# EE445L_Lab_7_Starter.net
KiCad netlist of a schematic drawn in EAGLE
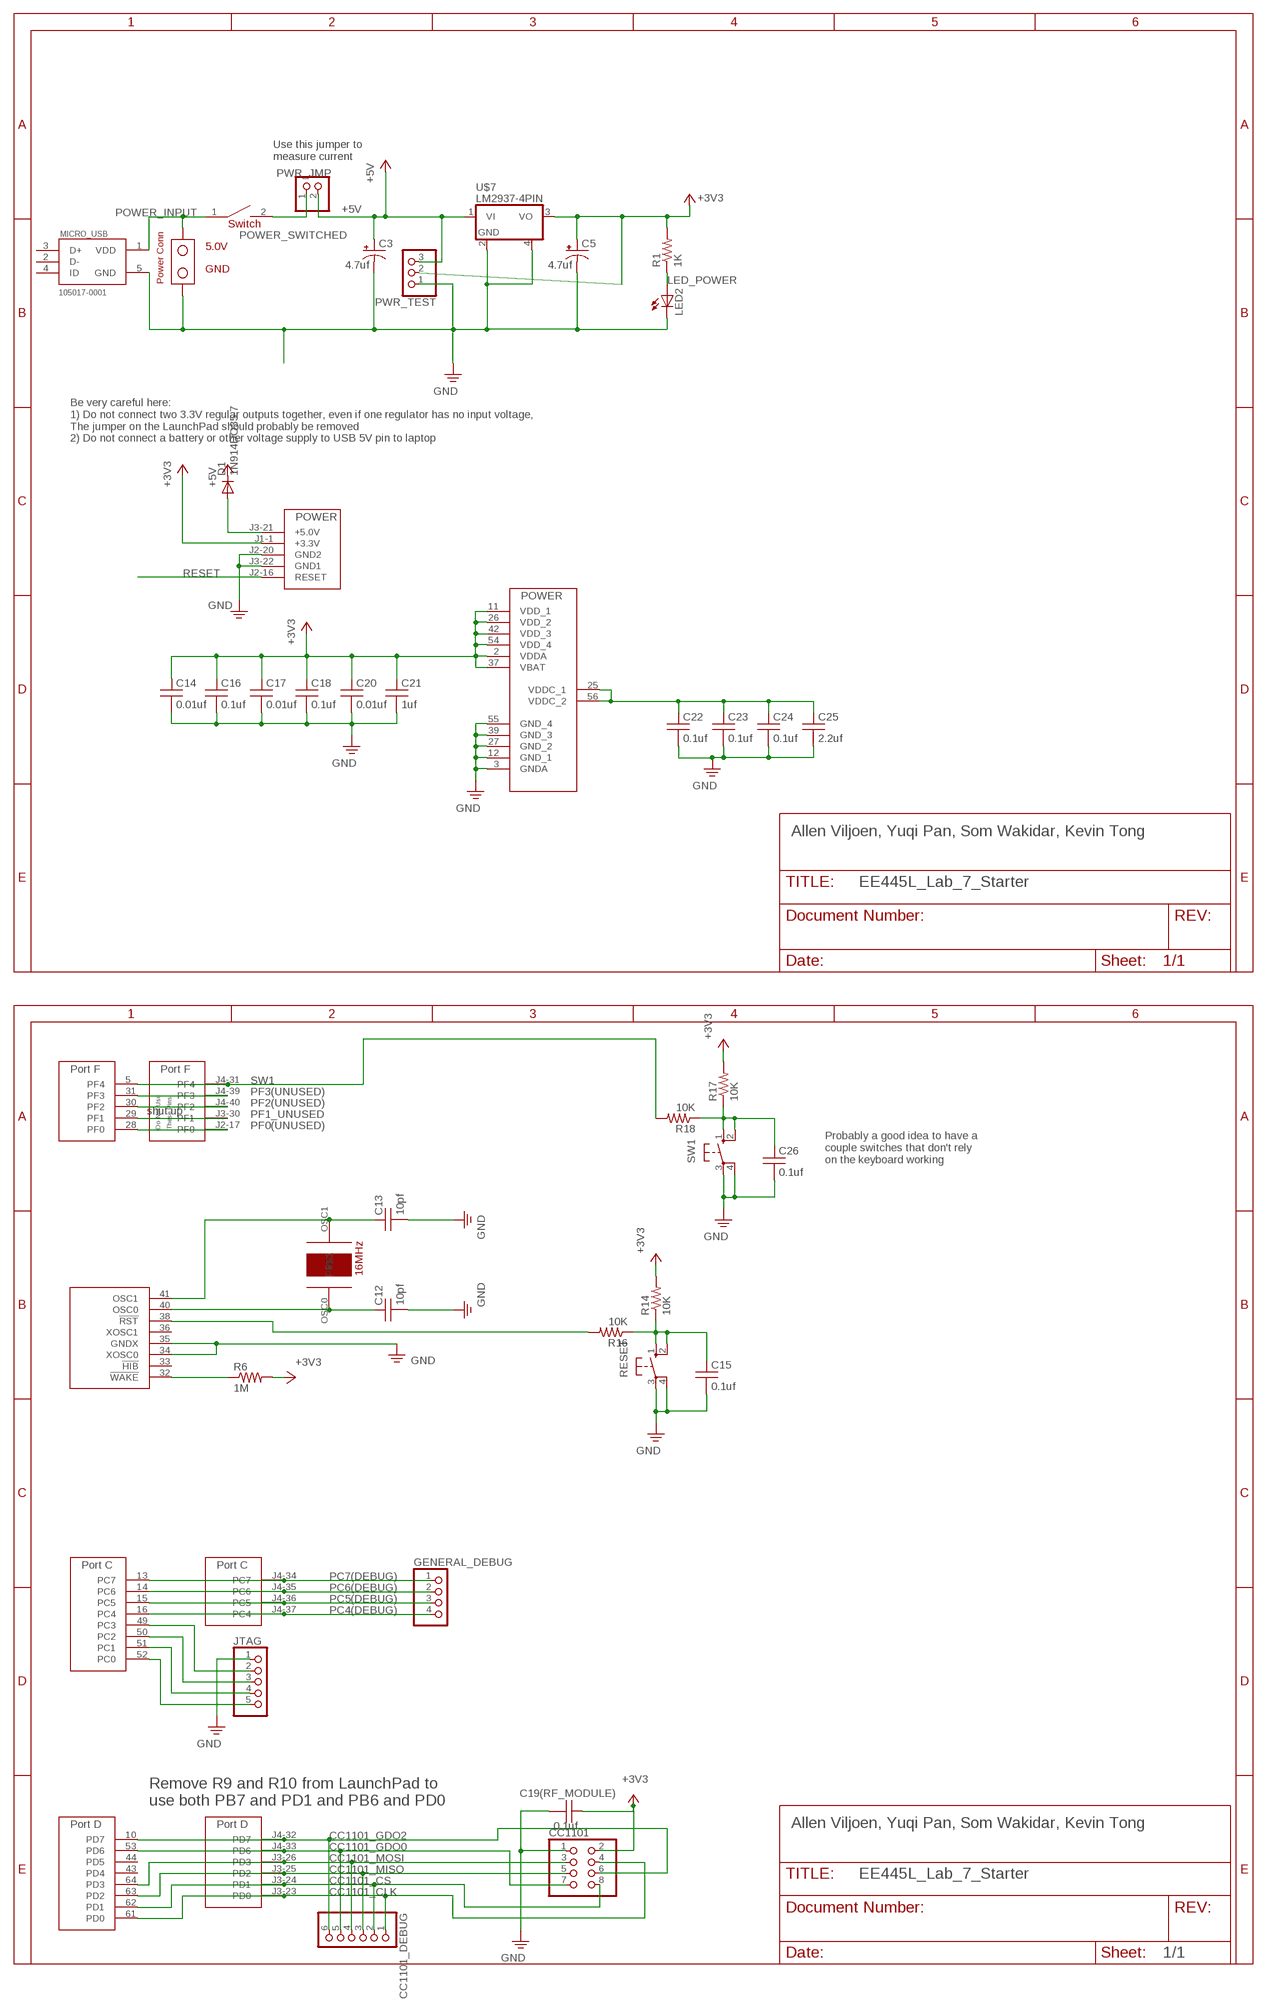
[diagram p0: schematic, sheet 1, part 1 of 2]
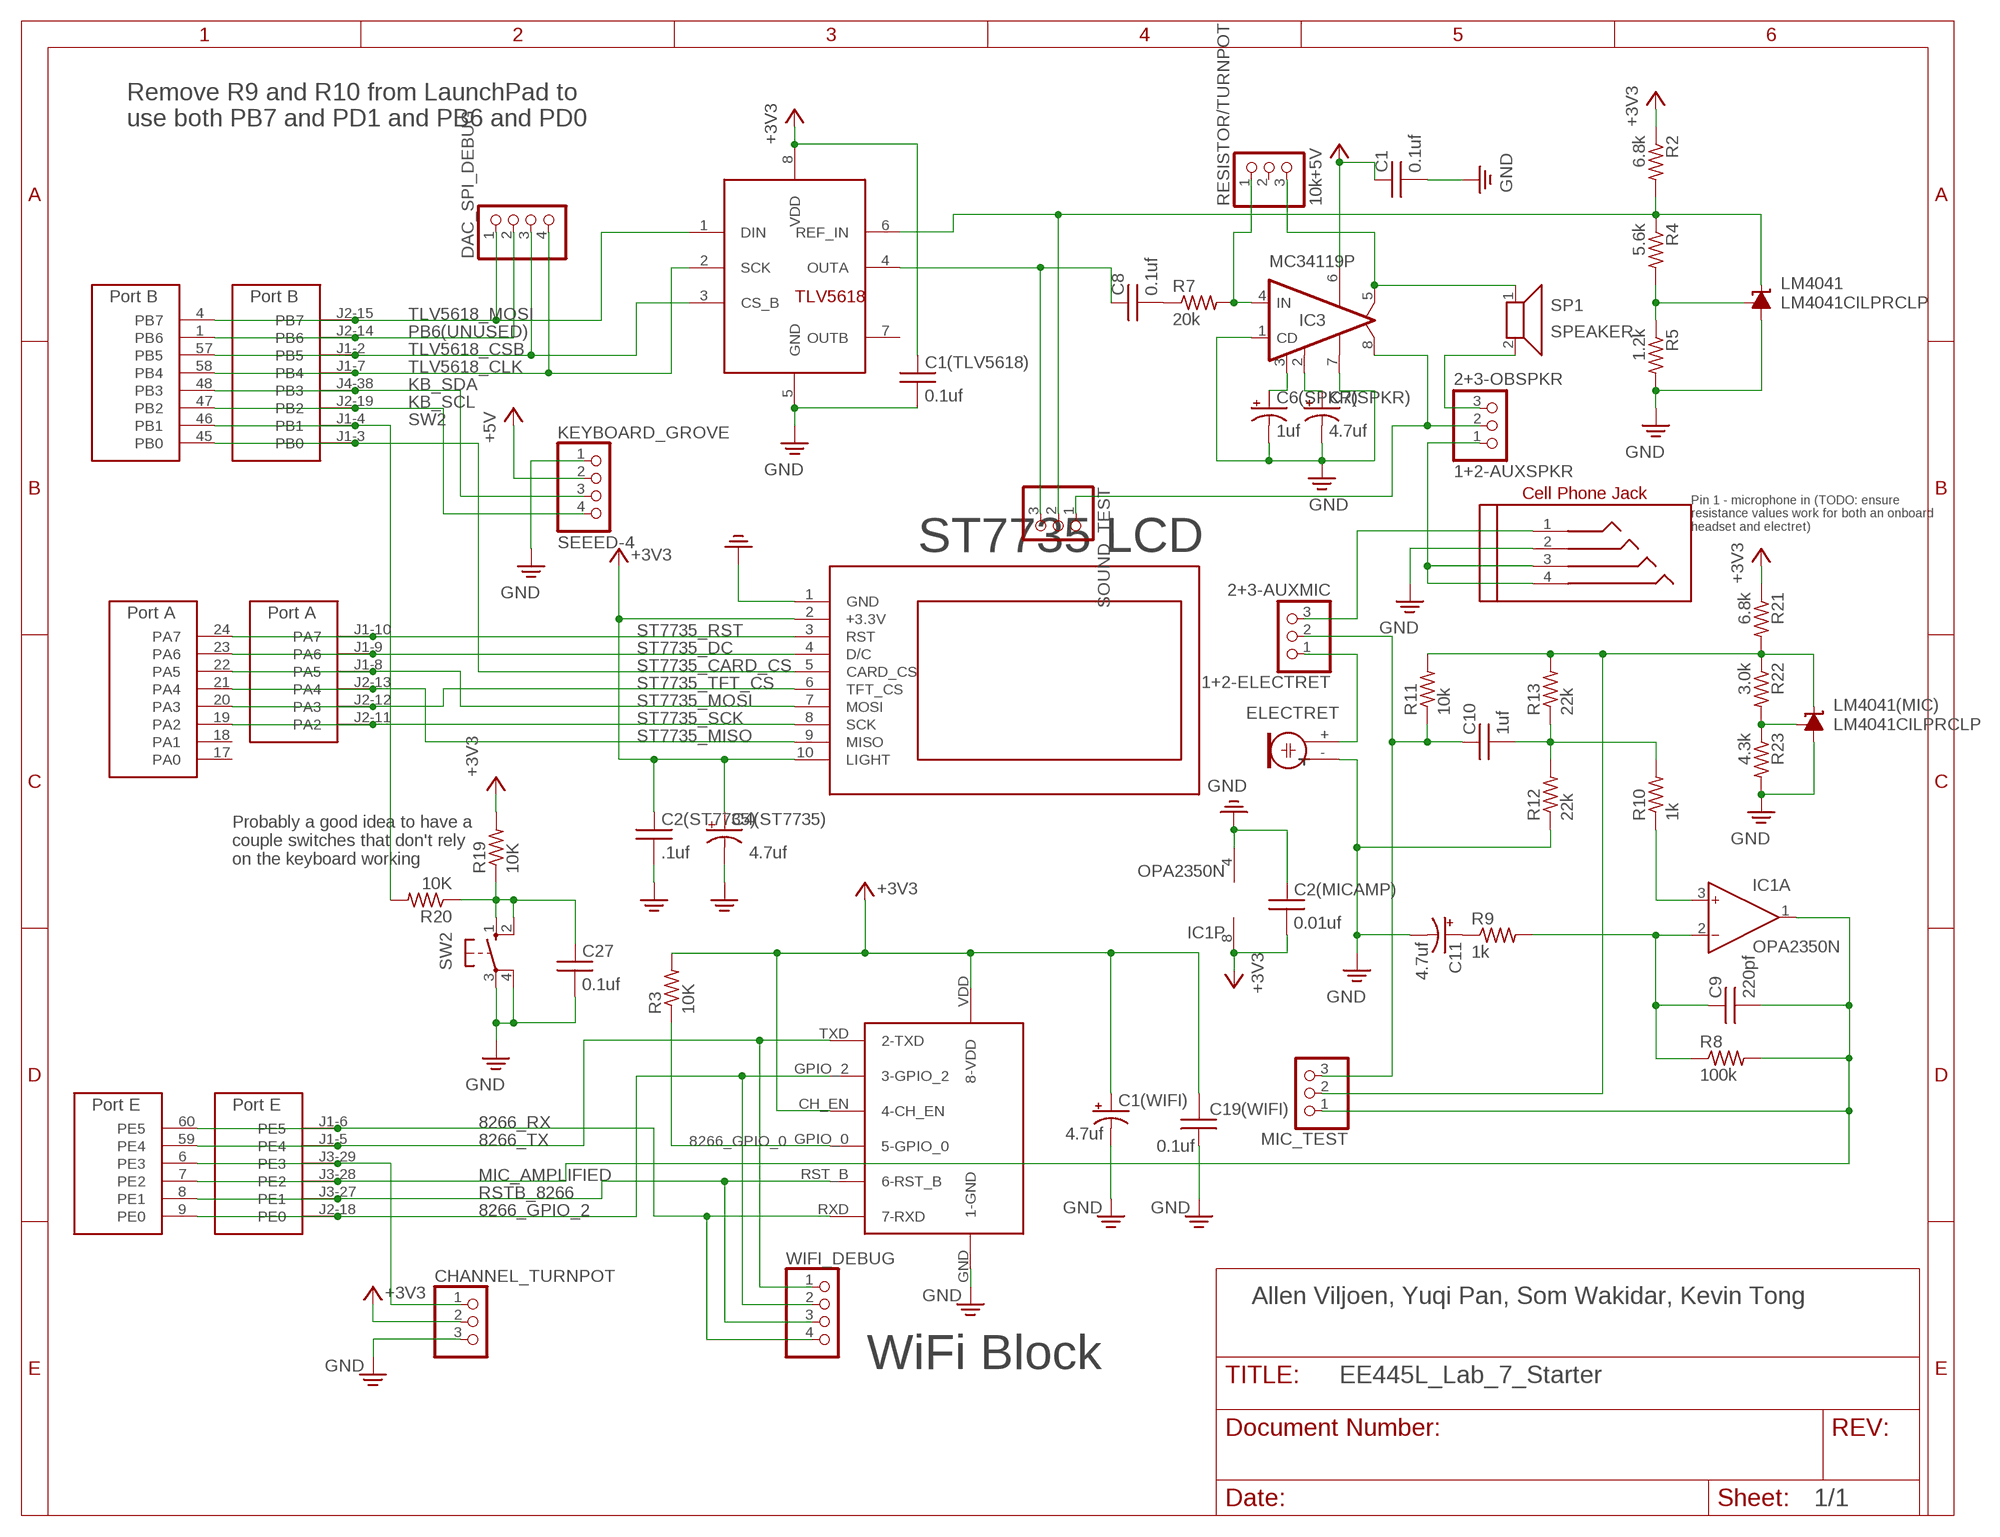
[diagram p1: schematic, sheet 1, part 2 of 2]

(export (version "E")
  (design (tool "Eeschema 10.0.6"))
  (components
    (comp (ref "1+2-AUXSPKR")
      (value "2+3-OBSPKR")
      (footprint "eagle-import:1X03")
      (libsource (lib "eagle-import") (part "PINHD-1X3"))
    )
    (comp (ref "1+2-ELECTRET")
      (value "2+3-AUXMIC")
      (footprint "eagle-import:1X03")
      (libsource (lib "eagle-import") (part "PINHD-1X3"))
    )
    (comp (ref "C1")
      (value "0.1uf")
      (footprint "eagle-import:CAP100MIL")
      (libsource (lib "eagle-import") (part "CAPACITOR025-024X044"))
    )
    (comp (ref "C1(TLV5618)")
      (value "0.1uf")
      (footprint "eagle-import:CAP200MIL")
      (libsource (lib "eagle-import") (part "CAPACITOR050-024X044"))
    )
    (comp (ref "C1(WIFI)")
      (value "4.7uf")
      (footprint "eagle-import:CAP200MILPOLARIZED")
      (libsource (lib "eagle-import") (part "CAPACITOR_POLARIZEDE5-6"))
    )
    (comp (ref "C2(MICAMP)")
      (value "0.01uf")
      (footprint "eagle-import:CAP200MIL")
      (libsource (lib "eagle-import") (part "CAPACITOR050-024X044"))
    )
    (comp (ref "C2(ST7735)")
      (value ".1uf")
      (footprint "eagle-import:CAP200MIL")
      (libsource (lib "eagle-import") (part "CAPACITOR050-024X044"))
    )
    (comp (ref "C3")
      (value "4.7uf")
      (footprint "eagle-import:CAP200MILPOLARIZED")
      (libsource (lib "eagle-import") (part "CAPACITOR_POLARIZEDE5-6"))
    )
    (comp (ref "C4(ST7735)")
      (value "4.7uf")
      (footprint "eagle-import:CAP200MILPOLARIZED")
      (libsource (lib "eagle-import") (part "CAPACITOR_POLARIZEDE5-6"))
    )
    (comp (ref "C5")
      (value "4.7uf")
      (footprint "eagle-import:CAP200MILPOLARIZED")
      (libsource (lib "eagle-import") (part "CAPACITOR_POLARIZEDE5-6"))
    )
    (comp (ref "C6(SPKR)")
      (value "1uf")
      (footprint "eagle-import:CAP200MILPOLARIZED")
      (libsource (lib "eagle-import") (part "CAPACITOR_POLARIZEDE5-6"))
    )
    (comp (ref "C7(SPKR)")
      (value "4.7uf")
      (footprint "eagle-import:CAP200MILPOLARIZED")
      (libsource (lib "eagle-import") (part "CAPACITOR_POLARIZEDE5-6"))
    )
    (comp (ref "C8")
      (value "0.1uf")
      (footprint "eagle-import:CAP100MIL")
      (libsource (lib "eagle-import") (part "CAPACITOR025-024X044"))
    )
    (comp (ref "C9")
      (value "220pf")
      (footprint "eagle-import:CAP200MIL")
      (libsource (lib "eagle-import") (part "CAPACITOR050-024X044"))
    )
    (comp (ref "C10")
      (value "1uf")
      (footprint "eagle-import:CAP200MIL")
      (libsource (lib "eagle-import") (part "CAPACITOR050-024X044"))
    )
    (comp (ref "C11")
      (value "4.7uf")
      (footprint "eagle-import:CAP200MILPOLARIZED")
      (libsource (lib "eagle-import") (part "CAPACITOR_POLARIZEDE5-6"))
    )
    (comp (ref "C12")
      (value "10pf")
      (footprint "eagle-import:CAP100MIL")
      (libsource (lib "eagle-import") (part "CAPACITOR025-024X044"))
    )
    (comp (ref "C13")
      (value "10pf")
      (footprint "eagle-import:CAP100MIL")
      (libsource (lib "eagle-import") (part "CAPACITOR025-024X044"))
    )
    (comp (ref "C14")
      (value "0.01uf")
      (footprint "eagle-import:CAP100MIL")
      (libsource (lib "eagle-import") (part "CAPACITOR025-024X044"))
    )
    (comp (ref "C15")
      (value "0.1uf")
      (footprint "eagle-import:CAP100MIL")
      (libsource (lib "eagle-import") (part "CAPACITOR025-024X044"))
    )
    (comp (ref "C16")
      (value "0.1uf")
      (footprint "eagle-import:CAP100MIL")
      (libsource (lib "eagle-import") (part "CAPACITOR025-024X044"))
    )
    (comp (ref "C17")
      (value "0.01uf")
      (footprint "eagle-import:CAP100MIL")
      (libsource (lib "eagle-import") (part "CAPACITOR025-024X044"))
    )
    (comp (ref "C18")
      (value "0.1uf")
      (footprint "eagle-import:CAP100MIL")
      (libsource (lib "eagle-import") (part "CAPACITOR025-024X044"))
    )
    (comp (ref "C19(RF_MODULE)")
      (value "0.1uf")
      (footprint "eagle-import:CAP100MIL")
      (libsource (lib "eagle-import") (part "CAPACITOR025-024X044"))
    )
    (comp (ref "C19(WIFI)")
      (value "0.1uf")
      (footprint "eagle-import:CAP200MIL")
      (libsource (lib "eagle-import") (part "CAPACITOR050-024X044"))
    )
    (comp (ref "C20")
      (value "0.01uf")
      (footprint "eagle-import:CAP100MIL")
      (libsource (lib "eagle-import") (part "CAPACITOR025-024X044"))
    )
    (comp (ref "C21")
      (value "1uf")
      (footprint "eagle-import:CAP100MIL")
      (libsource (lib "eagle-import") (part "CAPACITOR025-024X044"))
    )
    (comp (ref "C22")
      (value "0.1uf")
      (footprint "eagle-import:CAP100MIL")
      (libsource (lib "eagle-import") (part "CAPACITOR025-024X044"))
    )
    (comp (ref "C23")
      (value "0.1uf")
      (footprint "eagle-import:CAP100MIL")
      (libsource (lib "eagle-import") (part "CAPACITOR025-024X044"))
    )
    (comp (ref "C24")
      (value "0.1uf")
      (footprint "eagle-import:CAP100MIL")
      (libsource (lib "eagle-import") (part "CAPACITOR025-024X044"))
    )
    (comp (ref "C25")
      (value "2.2uf")
      (footprint "eagle-import:CAP100MIL")
      (libsource (lib "eagle-import") (part "CAPACITOR025-024X044"))
    )
    (comp (ref "C26")
      (value "0.1uf")
      (footprint "eagle-import:CAP100MIL")
      (libsource (lib "eagle-import") (part "CAPACITOR025-024X044"))
    )
    (comp (ref "C27")
      (value "0.1uf")
      (footprint "eagle-import:CAP100MIL")
      (libsource (lib "eagle-import") (part "CAPACITOR025-024X044"))
    )
    (comp (ref "CC1101")
      (value "PINHD-2X4")
      (footprint "eagle-import:2X04")
      (libsource (lib "eagle-import") (part "PINHD-2X4"))
    )
    (comp (ref "CC1101_DEBUG")
      (value "PINHD-1X6")
      (footprint "eagle-import:1X06")
      (libsource (lib "eagle-import") (part "PINHD-1X6"))
    )
    (comp (ref "CHANNEL_TURNPOT")
      (value "PINHD-1X3")
      (footprint "eagle-import:1X03")
      (libsource (lib "eagle-import") (part "PINHD-1X3"))
    )
    (comp (ref "D1")
      (value "1N914DO35-7")
      (footprint "eagle-import:DO35-7")
      (libsource (lib "eagle-import") (part "1N914DO35-7"))
    )
    (comp (ref "DAC_SPI_DEBUG")
      (value "PINHD-1X4/90")
      (footprint "eagle-import:1X04_90")
      (libsource (lib "eagle-import") (part "PINHD-1X4/90"))
    )
    (comp (ref "ELECTRET")
      (value "ELECTRET")
      (footprint "eagle-import:9.7ELECTRET")
      (libsource (lib "eagle-import") (part "ELECTRET"))
    )
    (comp (ref "GENERAL_DEBUG")
      (value "PINHD-1X4/90")
      (footprint "eagle-import:1X04_90")
      (libsource (lib "eagle-import") (part "PINHD-1X4/90"))
    )
    (comp (ref "IC1")
      (value "OPA2350N")
      (footprint "eagle-import:DIL08")
      (libsource (lib "eagle-import") (part "OPA2350N"))
    )
    (comp (ref "IC3")
      (value "MC34119P")
      (footprint "eagle-import:DIL08")
      (libsource (lib "eagle-import") (part "MC34119P"))
    )
    (comp (ref "JTAG")
      (value "PINHD-1X5")
      (footprint "eagle-import:1X05")
      (libsource (lib "eagle-import") (part "PINHD-1X5"))
    )
    (comp (ref "KEYBOARD_GROVE")
      (value "SEEED-4")
      (footprint "eagle-import:1_04X2MM")
      (libsource (lib "eagle-import") (part "SEEED-4"))
    )
    (comp (ref "LED2")
      (value "LED3MM")
      (footprint "eagle-import:LED3MM")
      (libsource (lib "eagle-import") (part "LED3MM"))
    )
    (comp (ref "LM4041")
      (value "LM4041CILPRCLP")
      (footprint "eagle-import:LP_O-PBCY-W3")
      (fields (field (name "MPN") "LM4041CILP"))
      (libsource (lib "eagle-import") (part "LM4041CILPRLPC"))
    )
    (comp (ref "LM4041(MIC)")
      (value "LM4041CILPRCLP")
      (footprint "eagle-import:LP_O-PBCY-W3")
      (fields (field (name "MPN") "LM4041CILP"))
      (libsource (lib "eagle-import") (part "LM4041CILPRLPC"))
    )
    (comp (ref "MICRO_USB")
      (value "105017-0001")
      (footprint "eagle-import:MOLEX_105017-0001")
      (fields (field (name "MF") "Molex"))
      (libsource (lib "eagle-import") (part "105017-0001"))
    )
    (comp (ref "MIC_TEST")
      (value "PINHD-1X3/90")
      (footprint "eagle-import:1X03_90")
      (libsource (lib "eagle-import") (part "PINHD-1X3/90"))
    )
    (comp (ref "PWR_JMP")
      (value "PINHD-1X2")
      (footprint "eagle-import:1X02")
      (libsource (lib "eagle-import") (part "PINHD-1X2"))
    )
    (comp (ref "PWR_TEST")
      (value "PINHD-1X3/90")
      (footprint "eagle-import:1X03_90")
      (libsource (lib "eagle-import") (part "PINHD-1X3/90"))
    )
    (comp (ref "R1")
      (value "1K")
      (footprint "eagle-import:RES200MIL")
      (libsource (lib "eagle-import") (part "RESISTOR0204/5"))
    )
    (comp (ref "R2")
      (value "6.8k")
      (footprint "eagle-import:RES300MIL")
      (libsource (lib "eagle-import") (part "RESISTOR0204/7"))
    )
    (comp (ref "R3")
      (value "10K")
      (footprint "eagle-import:RES300MIL")
      (libsource (lib "eagle-import") (part "RESISTOR0204/7"))
    )
    (comp (ref "R4")
      (value "5.6k")
      (footprint "eagle-import:RES300MIL")
      (libsource (lib "eagle-import") (part "RESISTOR0204/7"))
    )
    (comp (ref "R5")
      (value "1.2k")
      (footprint "eagle-import:RES300MIL")
      (libsource (lib "eagle-import") (part "RESISTOR0204/7"))
    )
    (comp (ref "R6")
      (value "1M")
      (footprint "eagle-import:RES300MIL")
      (libsource (lib "eagle-import") (part "RESISTOR0204/7"))
    )
    (comp (ref "R7")
      (value "20k")
      (footprint "eagle-import:RES300MIL")
      (libsource (lib "eagle-import") (part "RESISTOR0204/7"))
    )
    (comp (ref "R8")
      (value "100k")
      (footprint "eagle-import:RES300MIL")
      (libsource (lib "eagle-import") (part "RESISTOR0204/7"))
    )
    (comp (ref "R9")
      (value "1k")
      (footprint "eagle-import:RES300MIL")
      (libsource (lib "eagle-import") (part "RESISTOR0204/7"))
    )
    (comp (ref "R10")
      (value "1k")
      (footprint "eagle-import:RES300MIL")
      (libsource (lib "eagle-import") (part "RESISTOR0204/7"))
    )
    (comp (ref "R11")
      (value "10k")
      (footprint "eagle-import:RES300MIL")
      (libsource (lib "eagle-import") (part "RESISTOR0204/7"))
    )
    (comp (ref "R12")
      (value "22k")
      (footprint "eagle-import:RES300MIL")
      (libsource (lib "eagle-import") (part "RESISTOR0204/7"))
    )
    (comp (ref "R13")
      (value "22k")
      (footprint "eagle-import:RES300MIL")
      (libsource (lib "eagle-import") (part "RESISTOR0204/7"))
    )
    (comp (ref "R14")
      (value "10K")
      (footprint "eagle-import:RES200MIL")
      (libsource (lib "eagle-import") (part "RESISTOR0204/5"))
    )
    (comp (ref "R16")
      (value "10K")
      (footprint "eagle-import:RES200MIL")
      (libsource (lib "eagle-import") (part "RESISTOR0204/5"))
    )
    (comp (ref "R17")
      (value "10K")
      (footprint "eagle-import:RES200MIL")
      (libsource (lib "eagle-import") (part "RESISTOR0204/5"))
    )
    (comp (ref "R18")
      (value "10K")
      (footprint "eagle-import:RES200MIL")
      (libsource (lib "eagle-import") (part "RESISTOR0204/5"))
    )
    (comp (ref "R19")
      (value "10K")
      (footprint "eagle-import:RES200MIL")
      (libsource (lib "eagle-import") (part "RESISTOR0204/5"))
    )
    (comp (ref "R20")
      (value "10K")
      (footprint "eagle-import:RES200MIL")
      (libsource (lib "eagle-import") (part "RESISTOR0204/5"))
    )
    (comp (ref "R21")
      (value "6.8k")
      (footprint "eagle-import:RES300MIL")
      (libsource (lib "eagle-import") (part "RESISTOR0204/7"))
    )
    (comp (ref "R22")
      (value "3.0k")
      (footprint "eagle-import:RES300MIL")
      (libsource (lib "eagle-import") (part "RESISTOR0204/7"))
    )
    (comp (ref "R23")
      (value "4.3k")
      (footprint "eagle-import:RES300MIL")
      (libsource (lib "eagle-import") (part "RESISTOR0204/7"))
    )
    (comp (ref "RESET")
      (value "B3F-1052")
      (footprint "eagle-import:B3F-10XX")
      (fields (field (name "MPN") "B3F-1000"))
      (libsource (lib "eagle-import") (part "B3F-1052"))
    )
    (comp (ref "RESISTOR/TURNPOT")
      (value "10k")
      (footprint "eagle-import:1X03_90")
      (libsource (lib "eagle-import") (part "PINHD-1X3/90"))
    )
    (comp (ref "SOUND_TEST")
      (value "PINHD-1X3/90")
      (footprint "eagle-import:1X03_90")
      (libsource (lib "eagle-import") (part "PINHD-1X3/90"))
    )
    (comp (ref "SP1")
      (value "SPEAKER")
      (footprint "eagle-import:1X02")
      (libsource (lib "eagle-import") (part "SPEAKER"))
    )
    (comp (ref "ST7735")
      (value "ST7735")
      (footprint "eagle-import:ST7735")
      (libsource (lib "eagle-import") (part "ST7735"))
    )
    (comp (ref "SW1")
      (value "B3F-1052")
      (footprint "eagle-import:B3F-10XX")
      (fields (field (name "MPN") "B3F-1000"))
      (libsource (lib "eagle-import") (part "B3F-1052"))
    )
    (comp (ref "SW2")
      (value "B3F-1052")
      (footprint "eagle-import:B3F-10XX")
      (fields (field (name "MPN") "B3F-1000"))
      (libsource (lib "eagle-import") (part "B3F-1052"))
    )
    (comp (ref "TLV5618")
      (value "TLV5618")
      (footprint "eagle-import:DIL08")
      (libsource (lib "eagle-import") (part "TLV5618"))
    )
    (comp (ref "U$1")
      (value "ESP_8266")
      (footprint "eagle-import:ESP8266")
      (libsource (lib "eagle-import") (part "ESP_8266"))
    )
    (comp (ref "U$2")
      (value "TM4C_BP")
      (footprint "eagle-import:TM4C_BOOSTER_PACK")
      (libsource (lib "eagle-import") (part "TM4C_BP"))
    )
    (comp (ref "U$5")
      (value "POWER_CONN")
      (footprint "eagle-import:POWER_CONN")
      (libsource (lib "eagle-import") (part "POWER_CONN"))
    )
    (comp (ref "U$6")
      (value "SW_POWER_100MIL")
      (footprint "eagle-import:SW_POWER")
      (libsource (lib "eagle-import") (part "SW_POWER_100MIL"))
    )
    (comp (ref "U$7")
      (value "LM2937-4PIN")
      (footprint "eagle-import:TO220-4PIN")
      (libsource (lib "eagle-import") (part "LM2937-4PIN"))
    )
    (comp (ref "U$8")
      (value "AUDIO_CONN_3.5MM")
      (footprint "eagle-import:AUDIO_CONN_3.5MM")
      (libsource (lib "eagle-import") (part "AUDIO_CONN_3.5MM"))
    )
    (comp (ref "U$9")
      (value "TM4C123GH6PM")
      (footprint "eagle-import:QFP50P1200X1200X160-64N")
      (libsource (lib "eagle-import") (part "TM4C123GH6PM"))
    )
    (comp (ref "WIFI_DEBUG")
      (value "PINHD-1X4/90")
      (footprint "eagle-import:1X04_90")
      (libsource (lib "eagle-import") (part "PINHD-1X4/90"))
    )
    (comp (ref "Y1")
      (value "16MHZ_CRYSTAL")
      (footprint "eagle-import:16MHZ_CRYSTAL")
      (libsource (lib "eagle-import") (part "16MHZ_CRYSTAL"))
    )
  )
  (nets
    (net (code "1") (name "+3V3") (class "Default")
      (node (ref "C1(TLV5618)") (pin "1") (pinfunction "1_1") (pintype "passive"))
      (node (ref "C1(WIFI)") (pin "+") (pinfunction "+_+") (pintype "passive"))
      (node (ref "C14") (pin "1") (pinfunction "1_1") (pintype "passive"))
      (node (ref "C16") (pin "1") (pinfunction "1_1") (pintype "passive"))
      (node (ref "C17") (pin "1") (pinfunction "1_1") (pintype "passive"))
      (node (ref "C18") (pin "1") (pinfunction "1_1") (pintype "passive"))
      (node (ref "C19(RF_MODULE)") (pin "1") (pinfunction "1_1") (pintype "passive"))
      (node (ref "C19(WIFI)") (pin "2") (pinfunction "2_2") (pintype "passive"))
      (node (ref "C2(MICAMP)") (pin "2") (pinfunction "2_2") (pintype "passive"))
      (node (ref "C2(ST7735)") (pin "1") (pinfunction "1_1") (pintype "passive"))
      (node (ref "C20") (pin "1") (pinfunction "1_1") (pintype "passive"))
      (node (ref "C21") (pin "1") (pinfunction "1_1") (pintype "passive"))
      (node (ref "C4(ST7735)") (pin "+") (pinfunction "+_+") (pintype "passive"))
      (node (ref "C5") (pin "+") (pinfunction "+_+") (pintype "passive"))
      (node (ref "CC1101") (pin "2") (pinfunction "2_2") (pintype "passive"))
      (node (ref "CHANNEL_TURNPOT") (pin "2") (pinfunction "2_2") (pintype "passive"))
      (node (ref "IC1") (pin "8") (pinfunction "V+_8") (pintype "power_in"))
      (node (ref "PWR_TEST") (pin "2") (pinfunction "2_2") (pintype "passive"))
      (node (ref "R1") (pin "2") (pinfunction "2_2") (pintype "passive"))
      (node (ref "R14") (pin "2") (pinfunction "2_2") (pintype "passive"))
      (node (ref "R17") (pin "2") (pinfunction "2_2") (pintype "passive"))
      (node (ref "R19") (pin "2") (pinfunction "2_2") (pintype "passive"))
      (node (ref "R2") (pin "1") (pinfunction "1_1") (pintype "passive"))
      (node (ref "R21") (pin "1") (pinfunction "1_1") (pintype "passive"))
      (node (ref "R3") (pin "2") (pinfunction "2_2") (pintype "passive"))
      (node (ref "R6") (pin "2") (pinfunction "2_2") (pintype "passive"))
      (node (ref "ST7735") (pin "10") (pinfunction "LIGHT_10") (pintype "bidirectional"))
      (node (ref "ST7735") (pin "2") (pinfunction "+3.3V_2") (pintype "bidirectional"))
      (node (ref "TLV5618") (pin "8") (pinfunction "VDD_8") (pintype "bidirectional"))
      (node (ref "U$1") (pin "CH_EN") (pinfunction "4-CH_EN_CH_EN") (pintype "bidirectional"))
      (node (ref "U$1") (pin "VDD") (pinfunction "8-VDD_VDD") (pintype "bidirectional"))
      (node (ref "U$2") (pin "J1-1") (pinfunction "+3.3V_J1-1") (pintype "bidirectional"))
      (node (ref "U$7") (pin "3") (pinfunction "VO_3") (pintype "passive"))
      (node (ref "U$9") (pin "11") (pinfunction "VDD_1_11") (pintype "bidirectional"))
      (node (ref "U$9") (pin "2") (pinfunction "VDDA_2") (pintype "bidirectional"))
      (node (ref "U$9") (pin "26") (pinfunction "VDD_2_26") (pintype "bidirectional"))
      (node (ref "U$9") (pin "37") (pinfunction "VBAT_37") (pintype "bidirectional"))
      (node (ref "U$9") (pin "42") (pinfunction "VDD_3_42") (pintype "bidirectional"))
      (node (ref "U$9") (pin "54") (pinfunction "VDD_4_54") (pintype "bidirectional"))
    )
    (net (code "2") (name "+5V") (class "Default")
      (node (ref "C1") (pin "1") (pinfunction "1_1") (pintype "passive"))
      (node (ref "C3") (pin "+") (pinfunction "+_+") (pintype "passive"))
      (node (ref "D1") (pin "C") (pinfunction "C_C") (pintype "passive"))
      (node (ref "IC3") (pin "6") (pinfunction "VCC_6") (pintype "power_in"))
      (node (ref "KEYBOARD_GROVE") (pin "2") (pinfunction "2_2") (pintype "passive"))
      (node (ref "PWR_JMP") (pin "2") (pinfunction "2_2") (pintype "passive"))
      (node (ref "PWR_TEST") (pin "3") (pinfunction "3_3") (pintype "passive"))
      (node (ref "U$7") (pin "1") (pinfunction "VI_1") (pintype "input"))
    )
    (net (code "3") (name "/8266_GPIO_0") (class "Default")
      (node (ref "R3") (pin "1") (pinfunction "1_1") (pintype "passive"))
      (node (ref "U$1") (pin "GPIO_0") (pinfunction "5-GPIO_0_GPIO_0") (pintype "bidirectional"))
    )
    (net (code "4") (name "/8266_GPIO_2") (class "Default")
      (node (ref "U$1") (pin "GPIO_2") (pinfunction "3-GPIO_2_GPIO_2") (pintype "bidirectional"))
      (node (ref "U$2") (pin "J2-18") (pinfunction "PE0_J2-18") (pintype "bidirectional"))
      (node (ref "U$9") (pin "9") (pinfunction "PE0_9") (pintype "bidirectional"))
      (node (ref "WIFI_DEBUG") (pin "2") (pinfunction "2_2") (pintype "passive"))
    )
    (net (code "5") (name "/8266_RX") (class "Default")
      (node (ref "U$1") (pin "RXD") (pinfunction "7-RXD_RXD") (pintype "bidirectional"))
      (node (ref "U$2") (pin "J1-6") (pinfunction "PE5_J1-6") (pintype "bidirectional"))
      (node (ref "U$9") (pin "60") (pinfunction "PE5_60") (pintype "bidirectional"))
      (node (ref "WIFI_DEBUG") (pin "4") (pinfunction "4_4") (pintype "passive"))
    )
    (net (code "6") (name "/8266_TX") (class "Default")
      (node (ref "U$1") (pin "TXD") (pinfunction "2-TXD_TXD") (pintype "bidirectional"))
      (node (ref "U$2") (pin "J1-5") (pinfunction "PE4_J1-5") (pintype "bidirectional"))
      (node (ref "U$9") (pin "59") (pinfunction "PE4_59") (pintype "bidirectional"))
      (node (ref "WIFI_DEBUG") (pin "1") (pinfunction "1_1") (pintype "passive"))
    )
    (net (code "7") (name "/CC1101_CLK") (class "Default")
      (node (ref "CC1101") (pin "4") (pinfunction "4_4") (pintype "passive"))
      (node (ref "CC1101_DEBUG") (pin "1") (pinfunction "1_1") (pintype "passive"))
      (node (ref "U$2") (pin "J3-23") (pinfunction "PD0_J3-23") (pintype "bidirectional"))
      (node (ref "U$9") (pin "61") (pinfunction "PD0_61") (pintype "bidirectional"))
    )
    (net (code "8") (name "/CC1101_CS") (class "Default")
      (node (ref "CC1101") (pin "8") (pinfunction "8_8") (pintype "passive"))
      (node (ref "CC1101_DEBUG") (pin "2") (pinfunction "2_2") (pintype "passive"))
      (node (ref "U$2") (pin "J3-24") (pinfunction "PD1_J3-24") (pintype "bidirectional"))
      (node (ref "U$9") (pin "62") (pinfunction "PD1_62") (pintype "bidirectional"))
    )
    (net (code "9") (name "/CC1101_GDO0") (class "Default")
      (node (ref "CC1101") (pin "7") (pinfunction "7_7") (pintype "passive"))
      (node (ref "CC1101_DEBUG") (pin "5") (pinfunction "5_5") (pintype "passive"))
      (node (ref "U$2") (pin "J4-33") (pinfunction "PD6_J4-33") (pintype "bidirectional"))
      (node (ref "U$9") (pin "53") (pinfunction "PD6_53") (pintype "bidirectional"))
    )
    (net (code "10") (name "/CC1101_GDO2") (class "Default")
      (node (ref "CC1101") (pin "6") (pinfunction "6_6") (pintype "passive"))
      (node (ref "CC1101_DEBUG") (pin "6") (pinfunction "6_6") (pintype "passive"))
      (node (ref "U$2") (pin "J4-32") (pinfunction "PD7_J4-32") (pintype "bidirectional"))
      (node (ref "U$9") (pin "10") (pinfunction "PD7_10") (pintype "bidirectional"))
    )
    (net (code "11") (name "/CC1101_MISO") (class "Default")
      (node (ref "CC1101") (pin "5") (pinfunction "5_5") (pintype "passive"))
      (node (ref "CC1101_DEBUG") (pin "3") (pinfunction "3_3") (pintype "passive"))
      (node (ref "U$2") (pin "J3-25") (pinfunction "PD2_J3-25") (pintype "bidirectional"))
      (node (ref "U$9") (pin "63") (pinfunction "PD2_63") (pintype "bidirectional"))
    )
    (net (code "12") (name "/CC1101_MOSI") (class "Default")
      (node (ref "CC1101") (pin "3") (pinfunction "3_3") (pintype "passive"))
      (node (ref "CC1101_DEBUG") (pin "4") (pinfunction "4_4") (pintype "passive"))
      (node (ref "U$2") (pin "J3-26") (pinfunction "PD3_J3-26") (pintype "bidirectional"))
      (node (ref "U$9") (pin "64") (pinfunction "PD3_64") (pintype "bidirectional"))
    )
    (net (code "13") (name "/KB_SCL") (class "Default")
      (node (ref "KEYBOARD_GROVE") (pin "4") (pinfunction "4_4") (pintype "passive"))
      (node (ref "U$2") (pin "J2-19") (pinfunction "PB2_J2-19") (pintype "bidirectional"))
      (node (ref "U$9") (pin "47") (pinfunction "PB2_47") (pintype "bidirectional"))
    )
    (net (code "14") (name "/KB_SDA") (class "Default")
      (node (ref "KEYBOARD_GROVE") (pin "3") (pinfunction "3_3") (pintype "passive"))
      (node (ref "U$2") (pin "J4-38") (pinfunction "PB3_J4-38") (pintype "bidirectional"))
      (node (ref "U$9") (pin "48") (pinfunction "PB3_48") (pintype "bidirectional"))
    )
    (net (code "15") (name "/LED_POWER") (class "Default")
      (node (ref "LED2") (pin "A") (pinfunction "A_A") (pintype "passive"))
      (node (ref "R1") (pin "1") (pinfunction "1_1") (pintype "passive"))
    )
    (net (code "16") (name "/MIC_AMPLIFIED") (class "Default")
      (node (ref "C9") (pin "2") (pinfunction "2_2") (pintype "passive"))
      (node (ref "IC1") (pin "1") (pinfunction "OUT_1") (pintype "output"))
      (node (ref "MIC_TEST") (pin "1") (pinfunction "1_1") (pintype "passive"))
      (node (ref "R8") (pin "2") (pinfunction "2_2") (pintype "passive"))
      (node (ref "U$2") (pin "J3-28") (pinfunction "PE2_J3-28") (pintype "bidirectional"))
      (node (ref "U$9") (pin "7") (pinfunction "PE2_7") (pintype "bidirectional"))
    )
    (net (code "17") (name "/PB6(UNUSED)") (class "Default")
      (node (ref "DAC_SPI_DEBUG") (pin "2") (pinfunction "2_2") (pintype "passive"))
      (node (ref "U$2") (pin "J2-14") (pinfunction "PB6_J2-14") (pintype "bidirectional"))
      (node (ref "U$9") (pin "1") (pinfunction "PB6_1") (pintype "bidirectional"))
    )
    (net (code "18") (name "/PC4(DEBUG)") (class "Default")
      (node (ref "GENERAL_DEBUG") (pin "4") (pinfunction "4_4") (pintype "passive"))
      (node (ref "U$2") (pin "J4-37") (pinfunction "PC4_J4-37") (pintype "bidirectional"))
      (node (ref "U$9") (pin "16") (pinfunction "PC4_16") (pintype "bidirectional"))
    )
    (net (code "19") (name "/PC5(DEBUG)") (class "Default")
      (node (ref "GENERAL_DEBUG") (pin "3") (pinfunction "3_3") (pintype "passive"))
      (node (ref "U$2") (pin "J4-36") (pinfunction "PC5_J4-36") (pintype "bidirectional"))
      (node (ref "U$9") (pin "15") (pinfunction "PC5_15") (pintype "bidirectional"))
    )
    (net (code "20") (name "/PC6(DEBUG)") (class "Default")
      (node (ref "GENERAL_DEBUG") (pin "2") (pinfunction "2_2") (pintype "passive"))
      (node (ref "U$2") (pin "J4-35") (pinfunction "PC6_J4-35") (pintype "bidirectional"))
      (node (ref "U$9") (pin "14") (pinfunction "PC6_14") (pintype "bidirectional"))
    )
    (net (code "21") (name "/PC7(DEBUG)") (class "Default")
      (node (ref "GENERAL_DEBUG") (pin "1") (pinfunction "1_1") (pintype "passive"))
      (node (ref "U$2") (pin "J4-34") (pinfunction "PC7_J4-34") (pintype "bidirectional"))
      (node (ref "U$9") (pin "13") (pinfunction "PC7_13") (pintype "bidirectional"))
    )
    (net (code "22") (name "/PF0(UNUSED)") (class "Default")
      (node (ref "U$2") (pin "J2-17") (pinfunction "PF0_J2-17") (pintype "bidirectional"))
      (node (ref "U$9") (pin "28") (pinfunction "PF0_28") (pintype "bidirectional"))
    )
    (net (code "23") (name "/PF1_UNUSED") (class "Default")
      (node (ref "U$2") (pin "J3-30") (pinfunction "PF1_J3-30") (pintype "bidirectional"))
      (node (ref "U$9") (pin "29") (pinfunction "PF1_29") (pintype "bidirectional"))
    )
    (net (code "24") (name "/PF2(UNUSED)") (class "Default")
      (node (ref "U$2") (pin "J4-40") (pinfunction "PF2_J4-40") (pintype "bidirectional"))
      (node (ref "U$9") (pin "30") (pinfunction "PF2_30") (pintype "bidirectional"))
    )
    (net (code "25") (name "/PF3(UNUSED)") (class "Default")
      (node (ref "U$2") (pin "J4-39") (pinfunction "PF3_J4-39") (pintype "bidirectional"))
      (node (ref "U$9") (pin "31") (pinfunction "PF3_31") (pintype "bidirectional"))
    )
    (net (code "26") (name "/POWER_INPUT") (class "Default")
      (node (ref "MICRO_USB") (pin "1") (pinfunction "VDD_1") (pintype "power_in"))
      (node (ref "U$5") (pin "VDD") (pinfunction "VDD_VDD") (pintype "bidirectional"))
      (node (ref "U$6") (pin "1") (pinfunction "P$1_1") (pintype "bidirectional"))
    )
    (net (code "27") (name "/POWER_SWITCHED") (class "Default")
      (node (ref "PWR_JMP") (pin "1") (pinfunction "1_1") (pintype "passive"))
      (node (ref "U$6") (pin "2") (pinfunction "P$2_2") (pintype "bidirectional"))
    )
    (net (code "28") (name "/RESET") (class "Default")
      (node (ref "U$2") (pin "J2-16") (pinfunction "RESET_J2-16") (pintype "bidirectional"))
    )
    (net (code "29") (name "/RSTB_8266") (class "Default")
      (node (ref "U$1") (pin "RST_B") (pinfunction "6-RST_B_RST_B") (pintype "bidirectional"))
      (node (ref "U$2") (pin "J3-27") (pinfunction "PE1_J3-27") (pintype "bidirectional"))
      (node (ref "U$9") (pin "8") (pinfunction "PE1_8") (pintype "bidirectional"))
      (node (ref "WIFI_DEBUG") (pin "3") (pinfunction "3_3") (pintype "passive"))
    )
    (net (code "30") (name "/ST7735_CARD_CS") (class "Default")
      (node (ref "ST7735") (pin "5") (pinfunction "CARD_CS_5") (pintype "bidirectional"))
      (node (ref "U$2") (pin "J1-3") (pinfunction "PB0_J1-3") (pintype "bidirectional"))
      (node (ref "U$9") (pin "45") (pinfunction "PB0_45") (pintype "bidirectional"))
    )
    (net (code "31") (name "/ST7735_DC") (class "Default")
      (node (ref "ST7735") (pin "4") (pinfunction "D/C_4") (pintype "bidirectional"))
      (node (ref "U$2") (pin "J1-9") (pinfunction "PA6_J1-9") (pintype "bidirectional"))
      (node (ref "U$9") (pin "23") (pinfunction "PA6_23") (pintype "bidirectional"))
    )
    (net (code "32") (name "/ST7735_MISO") (class "Default")
      (node (ref "ST7735") (pin "9") (pinfunction "MISO_9") (pintype "bidirectional"))
      (node (ref "U$2") (pin "J2-13") (pinfunction "PA4_J2-13") (pintype "bidirectional"))
      (node (ref "U$9") (pin "21") (pinfunction "PA4_21") (pintype "bidirectional"))
    )
    (net (code "33") (name "/ST7735_MOSI") (class "Default")
      (node (ref "ST7735") (pin "7") (pinfunction "MOSI_7") (pintype "bidirectional"))
      (node (ref "U$2") (pin "J1-8") (pinfunction "PA5_J1-8") (pintype "bidirectional"))
      (node (ref "U$9") (pin "22") (pinfunction "PA5_22") (pintype "bidirectional"))
    )
    (net (code "34") (name "/ST7735_RST") (class "Default")
      (node (ref "ST7735") (pin "3") (pinfunction "RST_3") (pintype "bidirectional"))
      (node (ref "U$2") (pin "J1-10") (pinfunction "PA7_J1-10") (pintype "bidirectional"))
      (node (ref "U$9") (pin "24") (pinfunction "PA7_24") (pintype "bidirectional"))
    )
    (net (code "35") (name "/ST7735_SCK") (class "Default")
      (node (ref "ST7735") (pin "8") (pinfunction "SCK_8") (pintype "bidirectional"))
      (node (ref "U$2") (pin "J2-11") (pinfunction "PA2_J2-11") (pintype "bidirectional"))
      (node (ref "U$9") (pin "19") (pinfunction "PA2_19") (pintype "bidirectional"))
    )
    (net (code "36") (name "/ST7735_TFT_CS") (class "Default")
      (node (ref "ST7735") (pin "6") (pinfunction "TFT_CS_6") (pintype "bidirectional"))
      (node (ref "U$2") (pin "J2-12") (pinfunction "PA3_J2-12") (pintype "bidirectional"))
      (node (ref "U$9") (pin "20") (pinfunction "PA3_20") (pintype "bidirectional"))
    )
    (net (code "37") (name "/SW1") (class "Default")
      (node (ref "R18") (pin "2") (pinfunction "2_2") (pintype "passive"))
      (node (ref "U$2") (pin "J4-31") (pinfunction "PF4_J4-31") (pintype "bidirectional"))
      (node (ref "U$9") (pin "5") (pinfunction "PF4_5") (pintype "bidirectional"))
    )
    (net (code "38") (name "/SW2") (class "Default")
      (node (ref "R20") (pin "2") (pinfunction "2_2") (pintype "passive"))
      (node (ref "U$2") (pin "J1-4") (pinfunction "PB1_J1-4") (pintype "bidirectional"))
      (node (ref "U$9") (pin "46") (pinfunction "PB1_46") (pintype "bidirectional"))
    )
    (net (code "39") (name "/TLV5618_CLK") (class "Default")
      (node (ref "DAC_SPI_DEBUG") (pin "4") (pinfunction "4_4") (pintype "passive"))
      (node (ref "TLV5618") (pin "2") (pinfunction "SCK_2") (pintype "bidirectional"))
      (node (ref "U$2") (pin "J1-7") (pinfunction "PB4_J1-7") (pintype "bidirectional"))
      (node (ref "U$9") (pin "58") (pinfunction "PB4_58") (pintype "bidirectional"))
    )
    (net (code "40") (name "/TLV5618_CSB") (class "Default")
      (node (ref "DAC_SPI_DEBUG") (pin "3") (pinfunction "3_3") (pintype "passive"))
      (node (ref "TLV5618") (pin "3") (pinfunction "CS_B_3") (pintype "bidirectional"))
      (node (ref "U$2") (pin "J1-2") (pinfunction "PB5_J1-2") (pintype "bidirectional"))
      (node (ref "U$9") (pin "57") (pinfunction "PB5_57") (pintype "bidirectional"))
    )
    (net (code "41") (name "/TLV5618_MOSI") (class "Default")
      (node (ref "DAC_SPI_DEBUG") (pin "1") (pinfunction "1_1") (pintype "passive"))
      (node (ref "TLV5618") (pin "1") (pinfunction "DIN_1") (pintype "bidirectional"))
      (node (ref "U$2") (pin "J2-15") (pinfunction "PB7_J2-15") (pintype "bidirectional"))
      (node (ref "U$9") (pin "4") (pinfunction "PB7_4") (pintype "bidirectional"))
    )
    (net (code "42") (name "GND") (class "Default")
      (node (ref "C1") (pin "2") (pinfunction "2_2") (pintype "passive"))
      (node (ref "C1(TLV5618)") (pin "2") (pinfunction "2_2") (pintype "passive"))
      (node (ref "C1(WIFI)") (pin "-") (pinfunction "-_-") (pintype "passive"))
      (node (ref "C11") (pin "-") (pinfunction "-_-") (pintype "passive"))
      (node (ref "C12") (pin "2") (pinfunction "2_2") (pintype "passive"))
      (node (ref "C13") (pin "2") (pinfunction "2_2") (pintype "passive"))
      (node (ref "C14") (pin "2") (pinfunction "2_2") (pintype "passive"))
      (node (ref "C15") (pin "2") (pinfunction "2_2") (pintype "passive"))
      (node (ref "C16") (pin "2") (pinfunction "2_2") (pintype "passive"))
      (node (ref "C17") (pin "2") (pinfunction "2_2") (pintype "passive"))
      (node (ref "C18") (pin "2") (pinfunction "2_2") (pintype "passive"))
      (node (ref "C19(RF_MODULE)") (pin "2") (pinfunction "2_2") (pintype "passive"))
      (node (ref "C19(WIFI)") (pin "1") (pinfunction "1_1") (pintype "passive"))
      (node (ref "C2(MICAMP)") (pin "1") (pinfunction "1_1") (pintype "passive"))
      (node (ref "C2(ST7735)") (pin "2") (pinfunction "2_2") (pintype "passive"))
      (node (ref "C20") (pin "2") (pinfunction "2_2") (pintype "passive"))
      (node (ref "C21") (pin "2") (pinfunction "2_2") (pintype "passive"))
      (node (ref "C22") (pin "2") (pinfunction "2_2") (pintype "passive"))
      (node (ref "C23") (pin "2") (pinfunction "2_2") (pintype "passive"))
      (node (ref "C24") (pin "2") (pinfunction "2_2") (pintype "passive"))
      (node (ref "C25") (pin "2") (pinfunction "2_2") (pintype "passive"))
      (node (ref "C26") (pin "2") (pinfunction "2_2") (pintype "passive"))
      (node (ref "C27") (pin "2") (pinfunction "2_2") (pintype "passive"))
      (node (ref "C3") (pin "-") (pinfunction "-_-") (pintype "passive"))
      (node (ref "C4(ST7735)") (pin "-") (pinfunction "-_-") (pintype "passive"))
      (node (ref "C5") (pin "-") (pinfunction "-_-") (pintype "passive"))
      (node (ref "C6(SPKR)") (pin "-") (pinfunction "-_-") (pintype "passive"))
      (node (ref "C7(SPKR)") (pin "-") (pinfunction "-_-") (pintype "passive"))
      (node (ref "CC1101") (pin "1") (pinfunction "1_1") (pintype "passive"))
      (node (ref "CHANNEL_TURNPOT") (pin "3") (pinfunction "3_3") (pintype "passive"))
      (node (ref "ELECTRET") (pin "-") (pinfunction "1_-") (pintype "passive"))
      (node (ref "IC1") (pin "4") (pinfunction "V-_4") (pintype "power_in"))
      (node (ref "IC3") (pin "1") (pinfunction "CD_1") (pintype "passive"))
      (node (ref "IC3") (pin "7") (pinfunction "GND_7") (pintype "power_in"))
      (node (ref "JTAG") (pin "1") (pinfunction "1_1") (pintype "passive"))
      (node (ref "KEYBOARD_GROVE") (pin "1") (pinfunction "1_1") (pintype "passive"))
      (node (ref "LED2") (pin "K") (pinfunction "C_K") (pintype "passive"))
      (node (ref "LM4041") (pin "3") (pinfunction "A_3") (pintype "passive"))
      (node (ref "LM4041(MIC)") (pin "3") (pinfunction "A_3") (pintype "passive"))
      (node (ref "MICRO_USB") (pin "5") (pinfunction "GND_5") (pintype "power_in"))
      (node (ref "PWR_TEST") (pin "1") (pinfunction "1_1") (pintype "passive"))
      (node (ref "R12") (pin "1") (pinfunction "1_1") (pintype "passive"))
      (node (ref "R23") (pin "2") (pinfunction "2_2") (pintype "passive"))
      (node (ref "R5") (pin "2") (pinfunction "2_2") (pintype "passive"))
      (node (ref "RESET") (pin "3") (pinfunction "P_3") (pintype "passive"))
      (node (ref "RESET") (pin "4") (pinfunction "P1_4") (pintype "passive"))
      (node (ref "ST7735") (pin "1") (pinfunction "GND_1") (pintype "bidirectional"))
      (node (ref "SW1") (pin "3") (pinfunction "P_3") (pintype "passive"))
      (node (ref "SW1") (pin "4") (pinfunction "P1_4") (pintype "passive"))
      (node (ref "SW2") (pin "3") (pinfunction "P_3") (pintype "passive"))
      (node (ref "SW2") (pin "4") (pinfunction "P1_4") (pintype "passive"))
      (node (ref "TLV5618") (pin "5") (pinfunction "GND_5") (pintype "bidirectional"))
      (node (ref "U$1") (pin "GND") (pinfunction "1-GND_GND") (pintype "bidirectional"))
      (node (ref "U$2") (pin "J2-20") (pinfunction "GND2_J2-20") (pintype "bidirectional"))
      (node (ref "U$2") (pin "J3-22") (pinfunction "GND1_J3-22") (pintype "bidirectional"))
      (node (ref "U$5") (pin "GND") (pinfunction "GND_GND") (pintype "bidirectional"))
      (node (ref "U$7") (pin "2") (pinfunction "GND_2") (pintype "passive"))
      (node (ref "U$7") (pin "4") (pinfunction "PAD_4") (pintype "passive"))
      (node (ref "U$8") (pin "2") (pinfunction "2_2") (pintype "bidirectional"))
      (node (ref "U$9") (pin "12") (pinfunction "GND_1_12") (pintype "bidirectional"))
      (node (ref "U$9") (pin "27") (pinfunction "GND_2_27") (pintype "bidirectional"))
      (node (ref "U$9") (pin "3") (pinfunction "GNDA_3") (pintype "bidirectional"))
      (node (ref "U$9") (pin "34") (pinfunction "XOSC0_34") (pintype "bidirectional"))
      (node (ref "U$9") (pin "35") (pinfunction "GNDX_35") (pintype "bidirectional"))
      (node (ref "U$9") (pin "39") (pinfunction "GND_3_39") (pintype "bidirectional"))
      (node (ref "U$9") (pin "55") (pinfunction "GND_4_55") (pintype "bidirectional"))
    )
    (net (code "43") (name "Net-(1+2-AUXSPKR-Pad1)") (class "Default")
      (node (ref "1+2-AUXSPKR") (pin "1") (pinfunction "1_1") (pintype "passive"))
      (node (ref "U$8") (pin "3") (pinfunction "3_3") (pintype "bidirectional"))
      (node (ref "U$8") (pin "4") (pinfunction "4_4") (pintype "bidirectional"))
    )
    (net (code "44") (name "Net-(1+2-AUXSPKR-Pad3)") (class "Default")
      (node (ref "1+2-AUXSPKR") (pin "3") (pinfunction "3_3") (pintype "passive"))
      (node (ref "SP1") (pin "2") (pinfunction "2_2") (pintype "passive"))
    )
    (net (code "45") (name "Net-(1+2-ELECTRET-Pad2)") (class "Default")
      (node (ref "1+2-ELECTRET") (pin "2") (pinfunction "2_2") (pintype "passive"))
      (node (ref "C10") (pin "1") (pinfunction "1_1") (pintype "passive"))
      (node (ref "MIC_TEST") (pin "3") (pinfunction "3_3") (pintype "passive"))
      (node (ref "R11") (pin "1") (pinfunction "1_1") (pintype "passive"))
    )
    (net (code "46") (name "Net-(1+2-ELECTRET-Pad3)") (class "Default")
      (node (ref "1+2-ELECTRET") (pin "3") (pinfunction "3_3") (pintype "passive"))
      (node (ref "U$8") (pin "1") (pinfunction "1_1") (pintype "bidirectional"))
    )
    (net (code "47") (name "Net-(C8-Pad2)") (class "Default")
      (node (ref "C8") (pin "2") (pinfunction "2_2") (pintype "passive"))
      (node (ref "R7") (pin "1") (pinfunction "1_1") (pintype "passive"))
    )
    (net (code "48") (name "Net-(C10-Pad2)") (class "Default")
      (node (ref "C10") (pin "2") (pinfunction "2_2") (pintype "passive"))
      (node (ref "R10") (pin "2") (pinfunction "2_2") (pintype "passive"))
      (node (ref "R12") (pin "2") (pinfunction "2_2") (pintype "passive"))
      (node (ref "R13") (pin "1") (pinfunction "1_1") (pintype "passive"))
    )
    (net (code "49") (name "Net-(C11-Pad+)") (class "Default")
      (node (ref "C11") (pin "+") (pinfunction "+_+") (pintype "passive"))
      (node (ref "R9") (pin "1") (pinfunction "1_1") (pintype "passive"))
    )
    (net (code "50") (name "Net-(ELECTRET-2)") (class "Default")
      (node (ref "1+2-ELECTRET") (pin "1") (pinfunction "1_1") (pintype "passive"))
      (node (ref "ELECTRET") (pin "+") (pinfunction "2_+") (pintype "passive"))
    )
    (net (code "51") (name "Net-(IC1A-IN+)") (class "Default")
      (node (ref "IC1") (pin "3") (pinfunction "IN+_3") (pintype "input"))
      (node (ref "R10") (pin "1") (pinfunction "1_1") (pintype "passive"))
    )
    (net (code "52") (name "Net-(IC1A-IN-)") (class "Default")
      (node (ref "C9") (pin "1") (pinfunction "1_1") (pintype "passive"))
      (node (ref "IC1") (pin "2") (pinfunction "IN-_2") (pintype "input"))
      (node (ref "R8") (pin "1") (pinfunction "1_1") (pintype "passive"))
      (node (ref "R9") (pin "2") (pinfunction "2_2") (pintype "passive"))
    )
    (net (code "53") (name "Net-(IC3-FC1)") (class "Default")
      (node (ref "C6(SPKR)") (pin "+") (pinfunction "+_+") (pintype "passive"))
      (node (ref "IC3") (pin "3") (pinfunction "FC1_3") (pintype "passive"))
    )
    (net (code "54") (name "Net-(IC3-FC2)") (class "Default")
      (node (ref "C7(SPKR)") (pin "+") (pinfunction "+_+") (pintype "passive"))
      (node (ref "IC3") (pin "2") (pinfunction "FC2_2") (pintype "passive"))
    )
    (net (code "55") (name "Net-(IC3-IN)") (class "Default")
      (node (ref "IC3") (pin "4") (pinfunction "IN_4") (pintype "input"))
      (node (ref "R7") (pin "2") (pinfunction "2_2") (pintype "passive"))
      (node (ref "RESISTOR/TURNPOT") (pin "1") (pinfunction "1_1") (pintype "passive"))
    )
    (net (code "56") (name "Net-(IC3-VO1)") (class "Default")
      (node (ref "IC3") (pin "5") (pinfunction "VO1_5") (pintype "output"))
      (node (ref "RESISTOR/TURNPOT") (pin "3") (pinfunction "3_3") (pintype "passive"))
      (node (ref "SP1") (pin "1") (pinfunction "1_1") (pintype "passive"))
    )
    (net (code "57") (name "Net-(IC3-VO2)") (class "Default")
      (node (ref "1+2-AUXSPKR") (pin "2") (pinfunction "2_2") (pintype "passive"))
      (node (ref "IC3") (pin "8") (pinfunction "VO2_8") (pintype "output"))
      (node (ref "SOUND_TEST") (pin "1") (pinfunction "1_1") (pintype "passive"))
    )
    (net (code "58") (name "Net-(LM4041(MIC)-C)") (class "Default")
      (node (ref "LM4041(MIC)") (pin "2") (pinfunction "C_2") (pintype "passive"))
      (node (ref "MIC_TEST") (pin "2") (pinfunction "2_2") (pintype "passive"))
      (node (ref "R11") (pin "2") (pinfunction "2_2") (pintype "passive"))
      (node (ref "R13") (pin "2") (pinfunction "2_2") (pintype "passive"))
      (node (ref "R21") (pin "2") (pinfunction "2_2") (pintype "passive"))
      (node (ref "R22") (pin "1") (pinfunction "1_1") (pintype "passive"))
    )
    (net (code "59") (name "Net-(LM4041(MIC)-FB)") (class "Default")
      (node (ref "LM4041(MIC)") (pin "1") (pinfunction "FB_1") (pintype "passive"))
      (node (ref "R22") (pin "2") (pinfunction "2_2") (pintype "passive"))
      (node (ref "R23") (pin "1") (pinfunction "1_1") (pintype "passive"))
    )
    (net (code "60") (name "Net-(LM4041-C)") (class "Default")
      (node (ref "LM4041") (pin "2") (pinfunction "C_2") (pintype "passive"))
      (node (ref "R2") (pin "2") (pinfunction "2_2") (pintype "passive"))
      (node (ref "R4") (pin "1") (pinfunction "1_1") (pintype "passive"))
      (node (ref "SOUND_TEST") (pin "2") (pinfunction "2_2") (pintype "passive"))
      (node (ref "TLV5618") (pin "6") (pinfunction "REF_IN_6") (pintype "bidirectional"))
    )
    (net (code "61") (name "Net-(LM4041-FB)") (class "Default")
      (node (ref "LM4041") (pin "1") (pinfunction "FB_1") (pintype "passive"))
      (node (ref "R4") (pin "2") (pinfunction "2_2") (pintype "passive"))
      (node (ref "R5") (pin "1") (pinfunction "1_1") (pintype "passive"))
    )
    (net (code "62") (name "Net-(RESET-S)") (class "Default")
      (node (ref "C15") (pin "1") (pinfunction "1_1") (pintype "passive"))
      (node (ref "R14") (pin "1") (pinfunction "1_1") (pintype "passive"))
      (node (ref "R16") (pin "1") (pinfunction "1_1") (pintype "passive"))
      (node (ref "RESET") (pin "1") (pinfunction "S_1") (pintype "passive"))
      (node (ref "RESET") (pin "2") (pinfunction "S1_2") (pintype "passive"))
    )
    (net (code "63") (name "Net-(SW1-S)") (class "Default")
      (node (ref "C26") (pin "1") (pinfunction "1_1") (pintype "passive"))
      (node (ref "R17") (pin "1") (pinfunction "1_1") (pintype "passive"))
      (node (ref "R18") (pin "1") (pinfunction "1_1") (pintype "passive"))
      (node (ref "SW1") (pin "1") (pinfunction "S_1") (pintype "passive"))
      (node (ref "SW1") (pin "2") (pinfunction "S1_2") (pintype "passive"))
    )
    (net (code "64") (name "Net-(SW2-S)") (class "Default")
      (node (ref "C27") (pin "1") (pinfunction "1_1") (pintype "passive"))
      (node (ref "R19") (pin "1") (pinfunction "1_1") (pintype "passive"))
      (node (ref "R20") (pin "1") (pinfunction "1_1") (pintype "passive"))
      (node (ref "SW2") (pin "1") (pinfunction "S_1") (pintype "passive"))
      (node (ref "SW2") (pin "2") (pinfunction "S1_2") (pintype "passive"))
    )
    (net (code "65") (name "Net-(TLV5618-OUTA)") (class "Default")
      (node (ref "C8") (pin "1") (pinfunction "1_1") (pintype "passive"))
      (node (ref "SOUND_TEST") (pin "3") (pinfunction "3_3") (pintype "passive"))
      (node (ref "TLV5618") (pin "4") (pinfunction "OUTA_4") (pintype "bidirectional"))
    )
    (net (code "66") (name "Net-(U$2E-PE3)") (class "Default")
      (node (ref "CHANNEL_TURNPOT") (pin "1") (pinfunction "1_1") (pintype "passive"))
      (node (ref "U$2") (pin "J3-29") (pinfunction "PE3_J3-29") (pintype "bidirectional"))
      (node (ref "U$9") (pin "6") (pinfunction "PE3_6") (pintype "bidirectional"))
    )
    (net (code "67") (name "Net-(U$2G-+5.0V)") (class "Default")
      (node (ref "D1") (pin "A") (pinfunction "A_A") (pintype "passive"))
      (node (ref "U$2") (pin "J3-21") (pinfunction "+5.0V_J3-21") (pintype "bidirectional"))
    )
    (net (code "68") (name "Net-(U$9C-PC0)") (class "Default")
      (node (ref "JTAG") (pin "5") (pinfunction "5_5") (pintype "passive"))
      (node (ref "U$9") (pin "52") (pinfunction "PC0_52") (pintype "bidirectional"))
    )
    (net (code "69") (name "Net-(U$9C-PC1)") (class "Default")
      (node (ref "JTAG") (pin "4") (pinfunction "4_4") (pintype "passive"))
      (node (ref "U$9") (pin "51") (pinfunction "PC1_51") (pintype "bidirectional"))
    )
    (net (code "70") (name "Net-(U$9C-PC2)") (class "Default")
      (node (ref "JTAG") (pin "3") (pinfunction "3_3") (pintype "passive"))
      (node (ref "U$9") (pin "50") (pinfunction "PC2_50") (pintype "bidirectional"))
    )
    (net (code "71") (name "Net-(U$9C-PC3)") (class "Default")
      (node (ref "JTAG") (pin "2") (pinfunction "2_2") (pintype "passive"))
      (node (ref "U$9") (pin "49") (pinfunction "PC3_49") (pintype "bidirectional"))
    )
    (net (code "72") (name "Net-(U$9G-OSC0)") (class "Default")
      (node (ref "C12") (pin "1") (pinfunction "1_1") (pintype "passive"))
      (node (ref "U$9") (pin "40") (pinfunction "OSC0_40") (pintype "bidirectional"))
      (node (ref "Y1") (pin "OSC0") (pinfunction "P$1_OSC0") (pintype "bidirectional"))
    )
    (net (code "73") (name "Net-(U$9G-OSC1)") (class "Default")
      (node (ref "C13") (pin "1") (pinfunction "1_1") (pintype "passive"))
      (node (ref "U$9") (pin "41") (pinfunction "OSC1_41") (pintype "bidirectional"))
      (node (ref "Y1") (pin "OSC1") (pinfunction "P$2_OSC1") (pintype "bidirectional"))
    )
    (net (code "74") (name "Net-(U$9G-~{RST})") (class "Default")
      (node (ref "R16") (pin "2") (pinfunction "2_2") (pintype "passive"))
      (node (ref "U$9") (pin "38") (pinfunction "~{RST}_38") (pintype "bidirectional"))
    )
    (net (code "75") (name "Net-(U$9G-~{WAKE})") (class "Default")
      (node (ref "R6") (pin "1") (pinfunction "1_1") (pintype "passive"))
      (node (ref "U$9") (pin "32") (pinfunction "~{WAKE}_32") (pintype "bidirectional"))
    )
    (net (code "76") (name "Net-(U$9H-VDDC_1)") (class "Default")
      (node (ref "C22") (pin "1") (pinfunction "1_1") (pintype "passive"))
      (node (ref "C23") (pin "1") (pinfunction "1_1") (pintype "passive"))
      (node (ref "C24") (pin "1") (pinfunction "1_1") (pintype "passive"))
      (node (ref "C25") (pin "1") (pinfunction "1_1") (pintype "passive"))
      (node (ref "U$9") (pin "25") (pinfunction "VDDC_1_25") (pintype "bidirectional"))
      (node (ref "U$9") (pin "56") (pinfunction "VDDC_2_56") (pintype "bidirectional"))
    )
    (net (code "77") (name "unconnected-(MICRO_USB-D+-Pad3)") (class "Default")
      (node (ref "MICRO_USB") (pin "3") (pinfunction "D+_3") (pintype "bidirectional"))
    )
    (net (code "78") (name "unconnected-(MICRO_USB-D--Pad2)") (class "Default")
      (node (ref "MICRO_USB") (pin "2") (pinfunction "D-_2") (pintype "bidirectional"))
    )
    (net (code "79") (name "unconnected-(MICRO_USB-ID-Pad4)") (class "Default")
      (node (ref "MICRO_USB") (pin "4") (pinfunction "ID_4") (pintype "passive"))
    )
    (net (code "80") (name "unconnected-(RESISTOR/TURNPOT-Pad2)") (class "Default")
      (node (ref "RESISTOR/TURNPOT") (pin "2") (pinfunction "2_2") (pintype "passive"))
    )
    (net (code "81") (name "unconnected-(TLV5618-OUTB-Pad7)") (class "Default")
      (node (ref "TLV5618") (pin "7") (pinfunction "OUTB_7") (pintype "bidirectional"))
    )
    (net (code "82") (name "unconnected-(U$9A-PA0-Pad17)") (class "Default")
      (node (ref "U$9") (pin "17") (pinfunction "PA0_17") (pintype "bidirectional"))
    )
    (net (code "83") (name "unconnected-(U$9A-PA1-Pad18)") (class "Default")
      (node (ref "U$9") (pin "18") (pinfunction "PA1_18") (pintype "bidirectional"))
    )
    (net (code "84") (name "unconnected-(U$9D-PD4-Pad43)") (class "Default")
      (node (ref "U$9") (pin "43") (pinfunction "PD4_43") (pintype "bidirectional"))
    )
    (net (code "85") (name "unconnected-(U$9D-PD5-Pad44)") (class "Default")
      (node (ref "U$9") (pin "44") (pinfunction "PD5_44") (pintype "bidirectional"))
    )
    (net (code "86") (name "unconnected-(U$9G-XOSC1-Pad36)") (class "Default")
      (node (ref "U$9") (pin "36") (pinfunction "XOSC1_36") (pintype "bidirectional"))
    )
    (net (code "87") (name "unconnected-(U$9G-~{HIB}-Pad33)") (class "Default")
      (node (ref "U$9") (pin "33") (pinfunction "~{HIB}_33") (pintype "bidirectional"))
    )
  )
)
